# ESP8266EX.net
KiCad netlist of a schematic drawn in Altium Designer
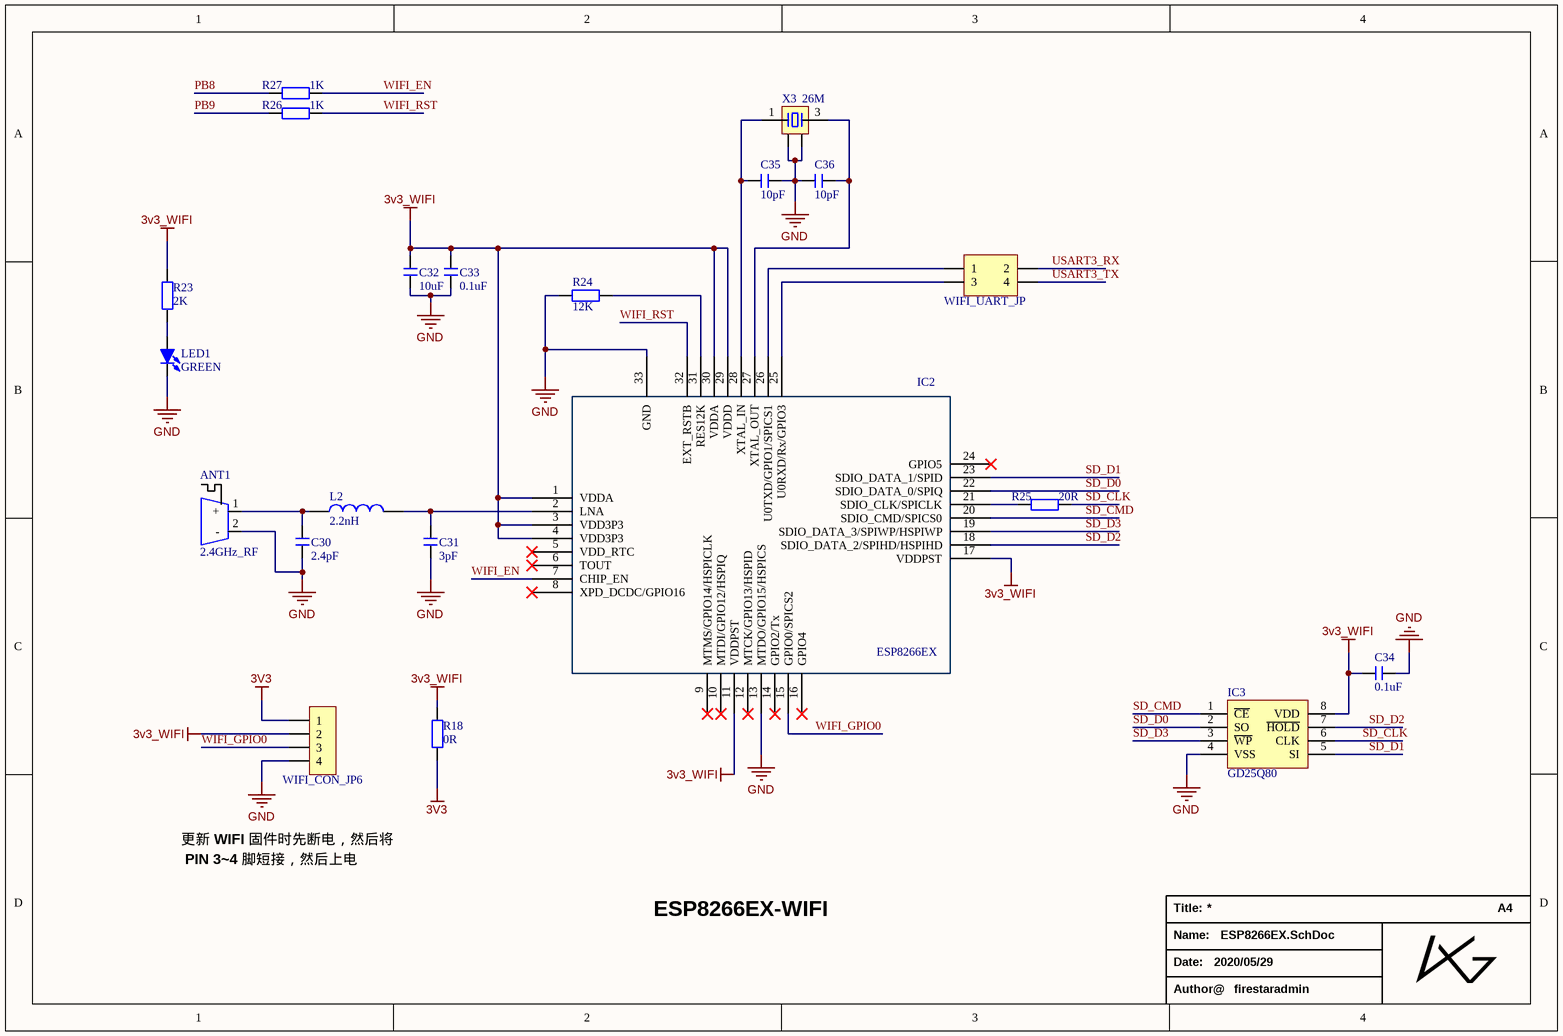
[diagram p0: ESP8266EX.SchDoc]

(export (version "E")
  (design (tool "Eeschema 10.0.6"))
  (components
    (comp (ref "ANT1")
      (value "2.4GHz_RF")
      (footprint "2.4G天线:ANT-F-1-2.4G")
      (libsource (lib "altium-import") (part "root_0_2.4GHz_RF_"))
    )
    (comp (ref "C30")
      (value "2.4pF")
      (footprint "C 0603_M")
      (description "无极性贴片电容")
      (fields (field (name "版权归属") "源创客"))
      (libsource (lib "altium-import") (part "root_3_C_"))
    )
    (comp (ref "C31")
      (value "3pF")
      (footprint "C 0603_M")
      (description "无极性贴片电容")
      (fields (field (name "版权归属") "源创客"))
      (libsource (lib "altium-import") (part "root_3_C_"))
    )
    (comp (ref "C32")
      (value "10uF")
      (footprint "C 0603_M")
      (description "无极性贴片电容")
      (fields (field (name "版权归属") "源创客"))
      (libsource (lib "altium-import") (part "root_3_C_"))
    )
    (comp (ref "C33")
      (value "0.1uF")
      (footprint "C 0603_M")
      (description "无极性贴片电容")
      (fields (field (name "版权归属") "源创客"))
      (libsource (lib "altium-import") (part "root_3_C_"))
    )
    (comp (ref "C34")
      (value "0.1uF")
      (footprint "C 0603_M")
      (description "无极性贴片电容")
      (fields (field (name "版权归属") "源创客"))
      (libsource (lib "altium-import") (part "root_0_C_"))
    )
    (comp (ref "C35")
      (value "10pF")
      (footprint "C 0603_M")
      (description "无极性贴片电容")
      (fields (field (name "版权归属") "源创客"))
      (libsource (lib "altium-import") (part "root_2_C_"))
    )
    (comp (ref "C36")
      (value "10pF")
      (footprint "C 0603_M")
      (description "无极性贴片电容")
      (fields (field (name "版权归属") "源创客"))
      (libsource (lib "altium-import") (part "root_2_C_"))
    )
    (comp (ref "IC2")
      (value "ESP8266EX")
      (footprint "QFN32 5x5_M")
      (description "WIFI-芯片")
      (fields (field (name "版权归属") "源创客"))
      (libsource (lib "altium-import") (part "root_0_ESP8266EX_"))
    )
    (comp (ref "IC3")
      (value "GD25Q80")
      (footprint "SOP8W_N")
      (description "外置Flash")
      (fields (field (name "版权归属") "源创客"))
      (libsource (lib "altium-import") (part "root_0_SST25VFxx_"))
    )
    (comp (ref "L2")
      (value "2.2nH")
      (footprint "L 0603")
      (description "小功率贴片电感")
      (fields (field (name "版权归属") "源创客"))
      (libsource (lib "altium-import") (part "root_0_L_"))
    )
    (comp (ref "LED1")
      (value "GREEN")
      (footprint "LED 0603G")
      (description "贴片LED")
      (fields (field (name "版权归属") "源创客"))
      (libsource (lib "altium-import") (part "root_0_LED-SMD_"))
    )
    (comp (ref "R18")
      (value "0R")
      (footprint "R 0603_M")
      (description "Resistor")
      (libsource (lib "") (part "RES_1"))
    )
    (comp (ref "R23")
      (value "2K")
      (footprint "R 0603_M")
      (description "Resistor")
      (libsource (lib "") (part "RES_1"))
    )
    (comp (ref "R24")
      (value "12K")
      (footprint "R 0603_M")
      (description "Resistor")
      (libsource (lib "General") (part "RES"))
    )
    (comp (ref "R25")
      (value "20R")
      (footprint "R 0603_M")
      (description "Resistor")
      (libsource (lib "General") (part "RES"))
    )
    (comp (ref "R26")
      (value "1K")
      (footprint "R 0603_M")
      (description "Resistor")
      (libsource (lib "General") (part "RES"))
    )
    (comp (ref "R27")
      (value "1K")
      (footprint "R 0603_M")
      (description "Resistor")
      (libsource (lib "General") (part "RES"))
    )
    (comp (ref "WIFI_CON_JP6")
      (value "HDR-1X4")
      (footprint "HDR2.54-LI-4P")
      (description "4P接插件")
      (fields (field (name "版权归属") "源创客"))
      (libsource (lib "altium-import") (part "root_0_Header 4_"))
    )
    (comp (ref "WIFI_UART_JP")
      (value "Header2X2")
      (footprint "HDR2.54-LI-2x2P")
      (description "2*2P接插件")
      (fields (field (name "版权归属") "源创客"))
      (libsource (lib "4.5   - 接插件-脚距2.54") (part "Header 2X2"))
    )
    (comp (ref "X3")
      (value "26M")
      (footprint "OSC 3225-4P")
      (description "4脚无源晶振")
      (fields (field (name "版权归属") "源创客"))
      (libsource (lib "altium-import") (part "root_0_XTAL-4P_"))
    )
  )
  (nets
    (net (code "1") (name "/PB8") (class "Default")
      (node (ref "R27") (pin "2") (pinfunction "2_2") (pintype "passive"))
    )
    (net (code "2") (name "/PB9") (class "Default")
      (node (ref "R26") (pin "2") (pinfunction "2_2") (pintype "passive"))
    )
    (net (code "3") (name "/SD_CLK") (class "Default")
      (node (ref "IC3") (pin "6") (pinfunction "CLK_6") (pintype "passive"))
      (node (ref "R25") (pin "1") (pinfunction "1_1") (pintype "passive"))
    )
    (net (code "4") (name "/SD_CMD") (class "Default")
      (node (ref "IC2") (pin "20") (pinfunction "SDIO_CMD/SPICS0_20") (pintype "passive"))
      (node (ref "IC3") (pin "1") (pinfunction "~{CE}_1") (pintype "passive"))
    )
    (net (code "5") (name "/SD_D0") (class "Default")
      (node (ref "IC2") (pin "22") (pinfunction "SDIO_DATA_0/SPIQ_22") (pintype "passive"))
      (node (ref "IC3") (pin "2") (pinfunction "SO_2") (pintype "passive"))
    )
    (net (code "6") (name "/SD_D1") (class "Default")
      (node (ref "IC2") (pin "23") (pinfunction "SDIO_DATA_1/SPID_23") (pintype "passive"))
      (node (ref "IC3") (pin "5") (pinfunction "SI_5") (pintype "passive"))
    )
    (net (code "7") (name "/SD_D2") (class "Default")
      (node (ref "IC2") (pin "18") (pinfunction "SDIO_DATA_2/SPIHD/HSPIHD_18") (pintype "passive"))
      (node (ref "IC3") (pin "7") (pinfunction "~{HOLD}_7") (pintype "passive"))
    )
    (net (code "8") (name "/SD_D3") (class "Default")
      (node (ref "IC2") (pin "19") (pinfunction "SDIO_DATA_3/SPIWP/HSPIWP_19") (pintype "passive"))
      (node (ref "IC3") (pin "3") (pinfunction "~{WP}_3") (pintype "passive"))
    )
    (net (code "9") (name "/USART3_RX") (class "Default")
      (node (ref "WIFI_UART_JP") (pin "2") (pinfunction "2_2") (pintype "passive"))
    )
    (net (code "10") (name "/USART3_TX") (class "Default")
      (node (ref "WIFI_UART_JP") (pin "4") (pinfunction "4_4") (pintype "passive"))
    )
    (net (code "11") (name "/WIFI_EN") (class "Default")
      (node (ref "IC2") (pin "7") (pinfunction "CHIP_EN_7") (pintype "passive"))
      (node (ref "R27") (pin "1") (pinfunction "1_1") (pintype "passive"))
    )
    (net (code "12") (name "/WIFI_GPIO0") (class "Default")
      (node (ref "IC2") (pin "15") (pinfunction "GPIO0/SPICS2_15") (pintype "passive"))
      (node (ref "WIFI_CON_JP6") (pin "3") (pinfunction "3_3") (pintype "passive"))
    )
    (net (code "13") (name "/WIFI_RST") (class "Default")
      (node (ref "IC2") (pin "32") (pinfunction "EXT_RSTB_32") (pintype "passive"))
      (node (ref "R26") (pin "1") (pinfunction "1_1") (pintype "passive"))
    )
    (net (code "14") (name "3V3") (class "Default")
      (node (ref "R18") (pin "1") (pinfunction "1_1") (pintype "passive"))
      (node (ref "WIFI_CON_JP6") (pin "1") (pinfunction "1_1") (pintype "passive"))
    )
    (net (code "15") (name "3v3_WIFI") (class "Default")
      (node (ref "C32") (pin "1") (pinfunction "1_1") (pintype "passive"))
      (node (ref "C33") (pin "1") (pinfunction "1_1") (pintype "passive"))
      (node (ref "C34") (pin "1") (pinfunction "1_1") (pintype "passive"))
      (node (ref "IC2") (pin "1") (pinfunction "VDDA_1") (pintype "passive"))
      (node (ref "IC2") (pin "11") (pinfunction "VDDPST_11") (pintype "passive"))
      (node (ref "IC2") (pin "17") (pinfunction "VDDPST_17") (pintype "passive"))
      (node (ref "IC2") (pin "29") (pinfunction "VDDD_29") (pintype "passive"))
      (node (ref "IC2") (pin "3") (pinfunction "VDD3P3_3") (pintype "passive"))
      (node (ref "IC2") (pin "30") (pinfunction "VDDA_30") (pintype "passive"))
      (node (ref "IC2") (pin "4") (pinfunction "VDD3P3_4") (pintype "passive"))
      (node (ref "IC3") (pin "8") (pinfunction "VDD_8") (pintype "passive"))
      (node (ref "R18") (pin "2") (pinfunction "2_2") (pintype "passive"))
      (node (ref "R23") (pin "2") (pinfunction "2_2") (pintype "passive"))
      (node (ref "WIFI_CON_JP6") (pin "2") (pinfunction "2_2") (pintype "passive"))
    )
    (net (code "16") (name "GND") (class "Default")
      (node (ref "ANT1") (pin "2") (pinfunction "-_2") (pintype "passive"))
      (node (ref "C30") (pin "2") (pinfunction "2_2") (pintype "passive"))
      (node (ref "C31") (pin "2") (pinfunction "2_2") (pintype "passive"))
      (node (ref "C32") (pin "2") (pinfunction "2_2") (pintype "passive"))
      (node (ref "C33") (pin "2") (pinfunction "2_2") (pintype "passive"))
      (node (ref "C34") (pin "2") (pinfunction "2_2") (pintype "passive"))
      (node (ref "C35") (pin "1") (pinfunction "1_1") (pintype "passive"))
      (node (ref "C36") (pin "2") (pinfunction "2_2") (pintype "passive"))
      (node (ref "IC2") (pin "13") (pinfunction "MTDO/GPIO15/HSPICS_13") (pintype "passive"))
      (node (ref "IC2") (pin "33") (pinfunction "GND_33") (pintype "passive"))
      (node (ref "IC3") (pin "4") (pinfunction "VSS_4") (pintype "passive"))
      (node (ref "LED1") (pin "2") (pinfunction "K_2") (pintype "passive"))
      (node (ref "R24") (pin "2") (pinfunction "2_2") (pintype "passive"))
      (node (ref "WIFI_CON_JP6") (pin "4") (pinfunction "4_4") (pintype "passive"))
      (node (ref "X3") (pin "2") (pinfunction "2_2") (pintype "passive"))
      (node (ref "X3") (pin "4") (pinfunction "4_4") (pintype "passive"))
    )
    (net (code "17") (name "Net-(ANT1-+)") (class "Default")
      (node (ref "ANT1") (pin "1") (pinfunction "+_1") (pintype "passive"))
      (node (ref "C30") (pin "1") (pinfunction "1_1") (pintype "passive"))
      (node (ref "L2") (pin "1") (pinfunction "1_1") (pintype "passive"))
    )
    (net (code "18") (name "Net-(IC2-LNA)") (class "Default")
      (node (ref "C31") (pin "1") (pinfunction "1_1") (pintype "passive"))
      (node (ref "IC2") (pin "2") (pinfunction "LNA_2") (pintype "passive"))
      (node (ref "L2") (pin "2") (pinfunction "2_2") (pintype "passive"))
    )
    (net (code "19") (name "Net-(IC2-RES12K)") (class "Default")
      (node (ref "IC2") (pin "31") (pinfunction "RES12K_31") (pintype "passive"))
      (node (ref "R24") (pin "1") (pinfunction "1_1") (pintype "passive"))
    )
    (net (code "20") (name "Net-(IC2-SDIO_CLK{slash}SPICLK)") (class "Default")
      (node (ref "IC2") (pin "21") (pinfunction "SDIO_CLK/SPICLK_21") (pintype "passive"))
      (node (ref "R25") (pin "2") (pinfunction "2_2") (pintype "passive"))
    )
    (net (code "21") (name "Net-(IC2-U0RXD{slash}Rx{slash}GPIO3)") (class "Default")
      (node (ref "IC2") (pin "25") (pinfunction "U0RXD/Rx/GPIO3_25") (pintype "passive"))
      (node (ref "WIFI_UART_JP") (pin "3") (pinfunction "3_3") (pintype "passive"))
    )
    (net (code "22") (name "Net-(IC2-U0TXD{slash}GPIO1{slash}SPICS1)") (class "Default")
      (node (ref "IC2") (pin "26") (pinfunction "U0TXD/GPIO1/SPICS1_26") (pintype "passive"))
      (node (ref "WIFI_UART_JP") (pin "1") (pinfunction "1_1") (pintype "passive"))
    )
    (net (code "23") (name "Net-(IC2-XTAL_IN)") (class "Default")
      (node (ref "C35") (pin "2") (pinfunction "2_2") (pintype "passive"))
      (node (ref "IC2") (pin "28") (pinfunction "XTAL_IN_28") (pintype "passive"))
      (node (ref "X3") (pin "1") (pinfunction "1_1") (pintype "passive"))
    )
    (net (code "24") (name "Net-(IC2-XTAL_OUT)") (class "Default")
      (node (ref "C36") (pin "1") (pinfunction "1_1") (pintype "passive"))
      (node (ref "IC2") (pin "27") (pinfunction "XTAL_OUT_27") (pintype "passive"))
      (node (ref "X3") (pin "3") (pinfunction "3_3") (pintype "passive"))
    )
    (net (code "25") (name "Net-(LED1-A)") (class "Default")
      (node (ref "LED1") (pin "1") (pinfunction "A_1") (pintype "passive"))
      (node (ref "R23") (pin "1") (pinfunction "1_1") (pintype "passive"))
    )
    (net (code "26") (name "unconnected-(IC2-GPIO2{slash}Tx-Pad14)") (class "Default")
      (node (ref "IC2") (pin "14") (pinfunction "GPIO2/Tx_14") (pintype "passive+no_connect"))
    )
    (net (code "27") (name "unconnected-(IC2-GPIO4-Pad16)") (class "Default")
      (node (ref "IC2") (pin "16") (pinfunction "GPIO4_16") (pintype "passive+no_connect"))
    )
    (net (code "28") (name "unconnected-(IC2-GPIO5-Pad24)") (class "Default")
      (node (ref "IC2") (pin "24") (pinfunction "GPIO5_24") (pintype "passive+no_connect"))
    )
    (net (code "29") (name "unconnected-(IC2-MTCK{slash}GPIO13{slash}HSPID-Pad12)") (class "Default")
      (node (ref "IC2") (pin "12") (pinfunction "MTCK/GPIO13/HSPID_12") (pintype "passive+no_connect"))
    )
    (net (code "30") (name "unconnected-(IC2-MTDI{slash}GPIO12{slash}HSPIQ-Pad10)") (class "Default")
      (node (ref "IC2") (pin "10") (pinfunction "MTDI/GPIO12/HSPIQ_10") (pintype "passive+no_connect"))
    )
    (net (code "31") (name "unconnected-(IC2-MTMS{slash}GPIO14{slash}HSPICLK-Pad9)") (class "Default")
      (node (ref "IC2") (pin "9") (pinfunction "MTMS/GPIO14/HSPICLK_9") (pintype "passive+no_connect"))
    )
    (net (code "32") (name "unconnected-(IC2-TOUT-Pad6)") (class "Default")
      (node (ref "IC2") (pin "6") (pinfunction "TOUT_6") (pintype "passive+no_connect"))
    )
    (net (code "33") (name "unconnected-(IC2-VDD_RTC-Pad5)") (class "Default")
      (node (ref "IC2") (pin "5") (pinfunction "VDD_RTC_5") (pintype "passive+no_connect"))
    )
    (net (code "34") (name "unconnected-(IC2-XPD_DCDC{slash}GPIO16-Pad8)") (class "Default")
      (node (ref "IC2") (pin "8") (pinfunction "XPD_DCDC/GPIO16_8") (pintype "passive+no_connect"))
    )
  )
)
